# STM.net
KiCad netlist of a schematic drawn in Altium Designer
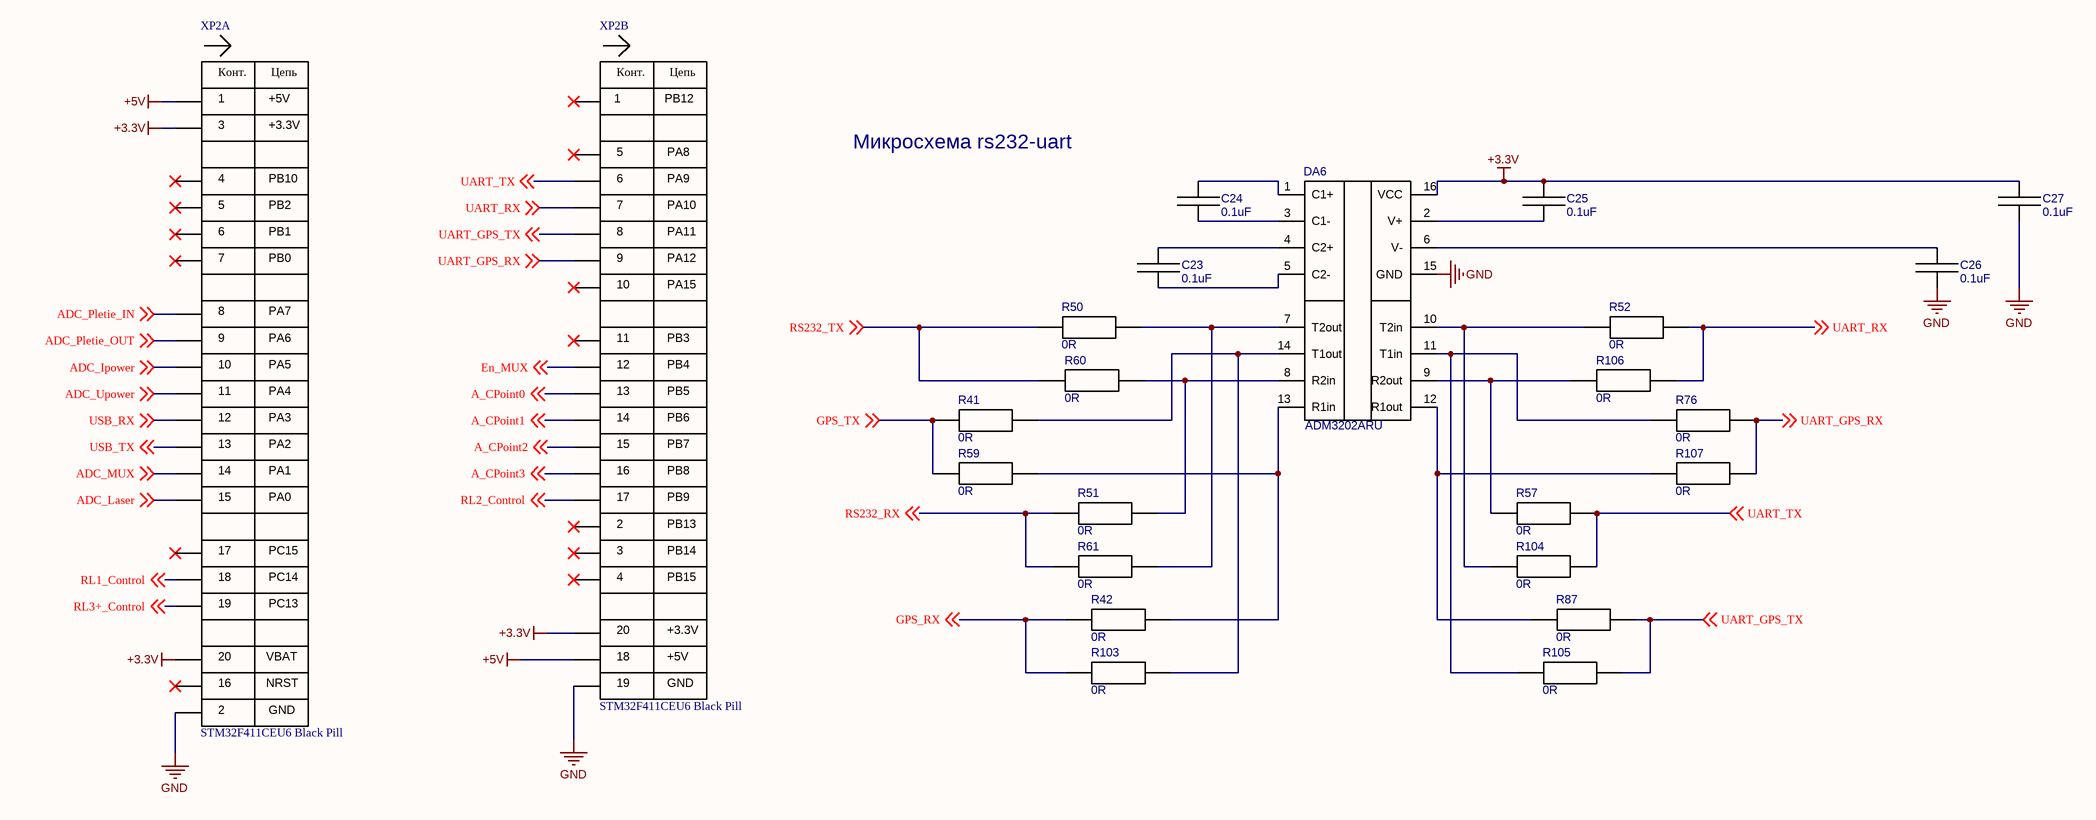
[diagram p0: STM.SchDoc]

(export (version "E")
  (design (tool "Eeschema 10.0.6"))
  (components
    (comp (ref "C23")
      (value "0.1uF")
      (footprint "0603C")
      (description "C0603 0.1UF 10% 50V")
      (fields
        (field (name "PART NUMBER") "SMD CAP CER 0.1UF ±10% 50V X7R 0603")
        (field (name "ADDED_BY") "anton@teslatec.ru")
      )
      (libsource (lib "Test_Stand_Pergam") (part "C0603-0.1UF 10% 50V"))
    )
    (comp (ref "C24")
      (value "0.1uF")
      (footprint "0603C")
      (description "C0603 0.1UF 10% 50V")
      (fields
        (field (name "PART NUMBER") "SMD CAP CER 0.1UF ±10% 50V X7R 0603")
        (field (name "ADDED_BY") "anton@teslatec.ru")
      )
      (libsource (lib "Test_Stand_Pergam") (part "C0603-0.1UF 10% 50V"))
    )
    (comp (ref "C25")
      (value "0.1uF")
      (footprint "0603C")
      (description "C0603 0.1UF 10% 50V")
      (fields
        (field (name "PART NUMBER") "SMD CAP CER 0.1UF ±10% 50V X7R 0603")
        (field (name "ADDED_BY") "anton@teslatec.ru")
      )
      (libsource (lib "Test_Stand_Pergam") (part "C0603-0.1UF 10% 50V"))
    )
    (comp (ref "C26")
      (value "0.1uF")
      (footprint "0603C")
      (description "C0603 0.1UF 10% 50V")
      (fields
        (field (name "PART NUMBER") "SMD CAP CER 0.1UF ±10% 50V X7R 0603")
        (field (name "ADDED_BY") "anton@teslatec.ru")
      )
      (libsource (lib "Test_Stand_Pergam") (part "C0603-0.1UF 10% 50V"))
    )
    (comp (ref "C27")
      (value "0.1uF")
      (footprint "0603C")
      (description "C0603 0.1UF 10% 50V")
      (fields
        (field (name "PART NUMBER") "SMD CAP CER 0.1UF ±10% 50V X7R 0603")
        (field (name "ADDED_BY") "anton@teslatec.ru")
      )
      (libsource (lib "Test_Stand_Pergam") (part "C0603-0.1UF 10% 50V"))
    )
    (comp (ref "DA6")
      (value "ADM3202ARU")
      (footprint "TSSOP-16")
      (description "Low Power, 3.3 V, RS-232\r\nLine Drivers/Receivers")
      (fields (field (name "ADDED_BY") "irdolgopolowa@yandex.ru"))
      (libsource (lib "Test_Stand_Pergam") (part "ADM3202ARU"))
    )
    (comp (ref "R41")
      (value "0R")
      (footprint "R0402")
      (description "Resistor SMD 0R 1% 0402")
      (fields
        (field (name "PART NUMBER") "SMD RES 0R 0402")
        (field (name "ADDED_BY") "irdolgopolowa@yandex.ru")
      )
      (libsource (lib "Test_Stand_Pergam") (part "R0402-0R"))
    )
    (comp (ref "R42")
      (value "0R")
      (footprint "R0402")
      (description "Resistor SMD 0R 1% 0402")
      (fields
        (field (name "PART NUMBER") "SMD RES 0R 0402")
        (field (name "ADDED_BY") "irdolgopolowa@yandex.ru")
      )
      (libsource (lib "Test_Stand_Pergam") (part "R0402-0R"))
    )
    (comp (ref "R50")
      (value "0R")
      (footprint "R0402")
      (description "Resistor SMD 0R 1% 0402")
      (fields
        (field (name "PART NUMBER") "SMD RES 0R 0402")
        (field (name "ADDED_BY") "irdolgopolowa@yandex.ru")
      )
      (libsource (lib "Test_Stand_Pergam") (part "R0402-0R"))
    )
    (comp (ref "R51")
      (value "0R")
      (footprint "R0402")
      (description "Resistor SMD 0R 1% 0402")
      (fields
        (field (name "PART NUMBER") "SMD RES 0R 0402")
        (field (name "ADDED_BY") "irdolgopolowa@yandex.ru")
      )
      (libsource (lib "Test_Stand_Pergam") (part "R0402-0R"))
    )
    (comp (ref "R52")
      (value "0R")
      (footprint "R0402")
      (description "Resistor SMD 0R 1% 0402")
      (fields
        (field (name "PART NUMBER") "SMD RES 0R 0402")
        (field (name "ADDED_BY") "irdolgopolowa@yandex.ru")
      )
      (libsource (lib "Test_Stand_Pergam") (part "R0402-0R"))
    )
    (comp (ref "R57")
      (value "0R")
      (footprint "R0402")
      (description "Resistor SMD 0R 1% 0402")
      (fields
        (field (name "PART NUMBER") "SMD RES 0R 0402")
        (field (name "ADDED_BY") "irdolgopolowa@yandex.ru")
      )
      (libsource (lib "Test_Stand_Pergam") (part "R0402-0R"))
    )
    (comp (ref "R59")
      (value "0R")
      (footprint "R0402")
      (description "Resistor SMD 0R 1% 0402")
      (fields
        (field (name "PART NUMBER") "SMD RES 0R 0402")
        (field (name "ADDED_BY") "irdolgopolowa@yandex.ru")
      )
      (libsource (lib "Test_Stand_Pergam") (part "R0402-0R"))
    )
    (comp (ref "R60")
      (value "0R")
      (footprint "R0402")
      (description "Resistor SMD 0R 1% 0402")
      (fields
        (field (name "PART NUMBER") "SMD RES 0R 0402")
        (field (name "ADDED_BY") "irdolgopolowa@yandex.ru")
      )
      (libsource (lib "Test_Stand_Pergam") (part "R0402-0R"))
    )
    (comp (ref "R61")
      (value "0R")
      (footprint "R0402")
      (description "Resistor SMD 0R 1% 0402")
      (fields
        (field (name "PART NUMBER") "SMD RES 0R 0402")
        (field (name "ADDED_BY") "irdolgopolowa@yandex.ru")
      )
      (libsource (lib "Test_Stand_Pergam") (part "R0402-0R"))
    )
    (comp (ref "R76")
      (value "0R")
      (footprint "R0402")
      (description "Resistor SMD 0R 1% 0402")
      (fields
        (field (name "PART NUMBER") "SMD RES 0R 0402")
        (field (name "ADDED_BY") "irdolgopolowa@yandex.ru")
      )
      (libsource (lib "Test_Stand_Pergam") (part "R0402-0R"))
    )
    (comp (ref "R87")
      (value "0R")
      (footprint "R0402")
      (description "Resistor SMD 0R 1% 0402")
      (fields
        (field (name "PART NUMBER") "SMD RES 0R 0402")
        (field (name "ADDED_BY") "irdolgopolowa@yandex.ru")
      )
      (libsource (lib "Test_Stand_Pergam") (part "R0402-0R"))
    )
    (comp (ref "R103")
      (value "0R")
      (footprint "R0402")
      (description "Resistor SMD 0R 1% 0402")
      (fields
        (field (name "PART NUMBER") "SMD RES 0R 0402")
        (field (name "ADDED_BY") "irdolgopolowa@yandex.ru")
      )
      (libsource (lib "Test_Stand_Pergam") (part "R0402-0R"))
    )
    (comp (ref "R104")
      (value "0R")
      (footprint "R0402")
      (description "Resistor SMD 0R 1% 0402")
      (fields
        (field (name "PART NUMBER") "SMD RES 0R 0402")
        (field (name "ADDED_BY") "irdolgopolowa@yandex.ru")
      )
      (libsource (lib "Test_Stand_Pergam") (part "R0402-0R"))
    )
    (comp (ref "R105")
      (value "0R")
      (footprint "R0402")
      (description "Resistor SMD 0R 1% 0402")
      (fields
        (field (name "PART NUMBER") "SMD RES 0R 0402")
        (field (name "ADDED_BY") "irdolgopolowa@yandex.ru")
      )
      (libsource (lib "Test_Stand_Pergam") (part "R0402-0R"))
    )
    (comp (ref "R106")
      (value "0R")
      (footprint "R0402")
      (description "Resistor SMD 0R 1% 0402")
      (fields
        (field (name "PART NUMBER") "SMD RES 0R 0402")
        (field (name "ADDED_BY") "irdolgopolowa@yandex.ru")
      )
      (libsource (lib "Test_Stand_Pergam") (part "R0402-0R"))
    )
    (comp (ref "R107")
      (value "0R")
      (footprint "R0402")
      (description "Resistor SMD 0R 1% 0402")
      (fields
        (field (name "PART NUMBER") "SMD RES 0R 0402")
        (field (name "ADDED_BY") "irdolgopolowa@yandex.ru")
      )
      (libsource (lib "Test_Stand_Pergam") (part "R0402-0R"))
    )
    (comp (ref "XP2")
      (value "STM32F411CEU6 Black Pill")
      (footprint "Black pill STM32F411CEU6")
      (description "STM32F411CEU6 Black pil")
      (fields
        (field (name "MATING PART") "2*DS1021-1*20SF11-B")
        (field (name "ADDED_BY") "irdolgopolowa@yandex.ru")
      )
      (libsource (lib "Test_Stand_Pergam") (part "STM32F411CEU6 Black pil"))
    )
  )
  (nets
    (net (code "1") (name "+3.3V") (class "Default")
      (node (ref "C25") (pin "2") (pinfunction "2_2") (pintype "passive"))
      (node (ref "C27") (pin "2") (pinfunction "2_2") (pintype "passive"))
      (node (ref "DA6") (pin "16") (pinfunction "VCC_16") (pintype "passive"))
      (node (ref "XP2") (pin "20") (pinfunction "VBAT_20") (pintype "passive"))
      (node (ref "XP2") (pin "3") (pinfunction "+3.3V_3") (pintype "passive"))
      (node (ref "XP2") (pin "40") (pinfunction "+3.3V_40") (pintype "passive"))
    )
    (net (code "2") (name "+5V") (class "Default")
      (node (ref "XP2") (pin "1") (pinfunction "+5V_1") (pintype "passive"))
      (node (ref "XP2") (pin "38") (pinfunction "+5V_38") (pintype "passive"))
    )
    (net (code "3") (name "ADC_Ipower") (class "Default")
      (node (ref "XP2") (pin "10") (pinfunction "PA5_10") (pintype "passive"))
    )
    (net (code "4") (name "ADC_Laser") (class "Default")
      (node (ref "XP2") (pin "15") (pinfunction "PA0_15") (pintype "passive"))
    )
    (net (code "5") (name "ADC_MUX") (class "Default")
      (node (ref "XP2") (pin "14") (pinfunction "PA1_14") (pintype "passive"))
    )
    (net (code "6") (name "ADC_Pletie_IN") (class "Default")
      (node (ref "XP2") (pin "8") (pinfunction "PA7_8") (pintype "passive"))
    )
    (net (code "7") (name "ADC_Pletie_OUT") (class "Default")
      (node (ref "XP2") (pin "9") (pinfunction "PA6_9") (pintype "passive"))
    )
    (net (code "8") (name "ADC_Upower") (class "Default")
      (node (ref "XP2") (pin "11") (pinfunction "PA4_11") (pintype "passive"))
    )
    (net (code "9") (name "A_CPoint0") (class "Default")
      (node (ref "XP2") (pin "33") (pinfunction "PB5_33") (pintype "passive"))
    )
    (net (code "10") (name "A_CPoint1") (class "Default")
      (node (ref "XP2") (pin "34") (pinfunction "PB6_34") (pintype "passive"))
    )
    (net (code "11") (name "A_CPoint2") (class "Default")
      (node (ref "XP2") (pin "35") (pinfunction "PB7_35") (pintype "passive"))
    )
    (net (code "12") (name "A_CPoint3") (class "Default")
      (node (ref "XP2") (pin "36") (pinfunction "PB8_36") (pintype "passive"))
    )
    (net (code "13") (name "En_MUX") (class "Default")
      (node (ref "XP2") (pin "32") (pinfunction "PB4_32") (pintype "passive"))
    )
    (net (code "14") (name "GND") (class "Default")
      (node (ref "C26") (pin "1") (pinfunction "1_1") (pintype "passive"))
      (node (ref "C27") (pin "1") (pinfunction "1_1") (pintype "passive"))
      (node (ref "DA6") (pin "15") (pinfunction "GND_15") (pintype "passive"))
      (node (ref "XP2") (pin "2") (pinfunction "GND_2") (pintype "passive"))
      (node (ref "XP2") (pin "39") (pinfunction "GND_39") (pintype "passive"))
    )
    (net (code "15") (name "GPS_RX") (class "Default")
      (node (ref "R103") (pin "1") (pinfunction "1_1") (pintype "passive"))
      (node (ref "R42") (pin "1") (pinfunction "1_1") (pintype "passive"))
    )
    (net (code "16") (name "GPS_TX") (class "Default")
      (node (ref "R41") (pin "1") (pinfunction "1_1") (pintype "passive"))
      (node (ref "R59") (pin "1") (pinfunction "1_1") (pintype "passive"))
    )
    (net (code "17") (name "Net-(DA6-C1+)") (class "Default")
      (node (ref "C24") (pin "2") (pinfunction "2_2") (pintype "passive"))
      (node (ref "DA6") (pin "1") (pinfunction "C1+_1") (pintype "passive"))
    )
    (net (code "18") (name "Net-(DA6-C1-)") (class "Default")
      (node (ref "C24") (pin "1") (pinfunction "1_1") (pintype "passive"))
      (node (ref "DA6") (pin "3") (pinfunction "C1-_3") (pintype "passive"))
    )
    (net (code "19") (name "Net-(DA6-C2+)") (class "Default")
      (node (ref "C23") (pin "2") (pinfunction "2_2") (pintype "passive"))
      (node (ref "DA6") (pin "4") (pinfunction "C2+_4") (pintype "passive"))
    )
    (net (code "20") (name "Net-(DA6-C2-)") (class "Default")
      (node (ref "C23") (pin "1") (pinfunction "1_1") (pintype "passive"))
      (node (ref "DA6") (pin "5") (pinfunction "C2-_5") (pintype "passive"))
    )
    (net (code "21") (name "Net-(DA6-R1in)") (class "Default")
      (node (ref "DA6") (pin "13") (pinfunction "R1in_13") (pintype "passive"))
      (node (ref "R42") (pin "2") (pinfunction "2_2") (pintype "passive"))
      (node (ref "R59") (pin "2") (pinfunction "2_2") (pintype "passive"))
    )
    (net (code "22") (name "Net-(DA6-R1out)") (class "Default")
      (node (ref "DA6") (pin "12") (pinfunction "R1out_12") (pintype "passive"))
      (node (ref "R107") (pin "1") (pinfunction "1_1") (pintype "passive"))
      (node (ref "R87") (pin "1") (pinfunction "1_1") (pintype "passive"))
    )
    (net (code "23") (name "Net-(DA6-R2in)") (class "Default")
      (node (ref "DA6") (pin "8") (pinfunction "R2in_8") (pintype "passive"))
      (node (ref "R51") (pin "2") (pinfunction "2_2") (pintype "passive"))
      (node (ref "R60") (pin "2") (pinfunction "2_2") (pintype "passive"))
    )
    (net (code "24") (name "Net-(DA6-R2out)") (class "Default")
      (node (ref "DA6") (pin "9") (pinfunction "R2out_9") (pintype "passive"))
      (node (ref "R106") (pin "1") (pinfunction "1_1") (pintype "passive"))
      (node (ref "R57") (pin "1") (pinfunction "1_1") (pintype "passive"))
    )
    (net (code "25") (name "Net-(DA6-T1in)") (class "Default")
      (node (ref "DA6") (pin "11") (pinfunction "T1in_11") (pintype "passive"))
      (node (ref "R105") (pin "1") (pinfunction "1_1") (pintype "passive"))
      (node (ref "R76") (pin "1") (pinfunction "1_1") (pintype "passive"))
    )
    (net (code "26") (name "Net-(DA6-T1out)") (class "Default")
      (node (ref "DA6") (pin "14") (pinfunction "T1out_14") (pintype "passive"))
      (node (ref "R103") (pin "2") (pinfunction "2_2") (pintype "passive"))
      (node (ref "R41") (pin "2") (pinfunction "2_2") (pintype "passive"))
    )
    (net (code "27") (name "Net-(DA6-T2in)") (class "Default")
      (node (ref "DA6") (pin "10") (pinfunction "T2in_10") (pintype "passive"))
      (node (ref "R104") (pin "1") (pinfunction "1_1") (pintype "passive"))
      (node (ref "R52") (pin "1") (pinfunction "1_1") (pintype "passive"))
    )
    (net (code "28") (name "Net-(DA6-T2out)") (class "Default")
      (node (ref "DA6") (pin "7") (pinfunction "T2out_7") (pintype "passive"))
      (node (ref "R50") (pin "2") (pinfunction "2_2") (pintype "passive"))
      (node (ref "R61") (pin "2") (pinfunction "2_2") (pintype "passive"))
    )
    (net (code "29") (name "Net-(DA6-V+)") (class "Default")
      (node (ref "C25") (pin "1") (pinfunction "1_1") (pintype "passive"))
      (node (ref "DA6") (pin "2") (pinfunction "V+_2") (pintype "passive"))
    )
    (net (code "30") (name "Net-(DA6-V-)") (class "Default")
      (node (ref "C26") (pin "2") (pinfunction "2_2") (pintype "passive"))
      (node (ref "DA6") (pin "6") (pinfunction "V-_6") (pintype "passive"))
    )
    (net (code "31") (name "RL1_Control") (class "Default")
      (node (ref "XP2") (pin "18") (pinfunction "PC14_18") (pintype "passive"))
    )
    (net (code "32") (name "RL2_Control") (class "Default")
      (node (ref "XP2") (pin "37") (pinfunction "PB9_37") (pintype "passive"))
    )
    (net (code "33") (name "RL3+_Control") (class "Default")
      (node (ref "XP2") (pin "19") (pinfunction "PC13_19") (pintype "passive"))
    )
    (net (code "34") (name "RS232_RX") (class "Default")
      (node (ref "R51") (pin "1") (pinfunction "1_1") (pintype "passive"))
      (node (ref "R61") (pin "1") (pinfunction "1_1") (pintype "passive"))
    )
    (net (code "35") (name "RS232_TX") (class "Default")
      (node (ref "R50") (pin "1") (pinfunction "1_1") (pintype "passive"))
      (node (ref "R60") (pin "1") (pinfunction "1_1") (pintype "passive"))
    )
    (net (code "36") (name "UART_GPS_RX") (class "Default")
      (node (ref "R107") (pin "2") (pinfunction "2_2") (pintype "passive"))
      (node (ref "R76") (pin "2") (pinfunction "2_2") (pintype "passive"))
      (node (ref "XP2") (pin "29") (pinfunction "PA12_29") (pintype "passive"))
    )
    (net (code "37") (name "UART_GPS_TX") (class "Default")
      (node (ref "R105") (pin "2") (pinfunction "2_2") (pintype "passive"))
      (node (ref "R87") (pin "2") (pinfunction "2_2") (pintype "passive"))
      (node (ref "XP2") (pin "28") (pinfunction "PA11_28") (pintype "passive"))
    )
    (net (code "38") (name "UART_RX") (class "Default")
      (node (ref "R106") (pin "2") (pinfunction "2_2") (pintype "passive"))
      (node (ref "R52") (pin "2") (pinfunction "2_2") (pintype "passive"))
      (node (ref "XP2") (pin "27") (pinfunction "PA10_27") (pintype "passive"))
    )
    (net (code "39") (name "UART_TX") (class "Default")
      (node (ref "R104") (pin "2") (pinfunction "2_2") (pintype "passive"))
      (node (ref "R57") (pin "2") (pinfunction "2_2") (pintype "passive"))
      (node (ref "XP2") (pin "26") (pinfunction "PA9_26") (pintype "passive"))
    )
    (net (code "40") (name "USB_RX") (class "Default")
      (node (ref "XP2") (pin "12") (pinfunction "PA3_12") (pintype "passive"))
    )
    (net (code "41") (name "USB_TX") (class "Default")
      (node (ref "XP2") (pin "13") (pinfunction "PA2_13") (pintype "passive"))
    )
    (net (code "42") (name "unconnected-(XP2A-NRST-Pad16)") (class "Default")
      (node (ref "XP2") (pin "16") (pinfunction "NRST_16") (pintype "passive+no_connect"))
    )
    (net (code "43") (name "unconnected-(XP2A-PB0-Pad7)") (class "Default")
      (node (ref "XP2") (pin "7") (pinfunction "PB0_7") (pintype "passive+no_connect"))
    )
    (net (code "44") (name "unconnected-(XP2A-PB1-Pad6)") (class "Default")
      (node (ref "XP2") (pin "6") (pinfunction "PB1_6") (pintype "passive+no_connect"))
    )
    (net (code "45") (name "unconnected-(XP2A-PB2-Pad5)") (class "Default")
      (node (ref "XP2") (pin "5") (pinfunction "PB2_5") (pintype "passive+no_connect"))
    )
    (net (code "46") (name "unconnected-(XP2A-PB10-Pad4)") (class "Default")
      (node (ref "XP2") (pin "4") (pinfunction "PB10_4") (pintype "passive+no_connect"))
    )
    (net (code "47") (name "unconnected-(XP2A-PC15-Pad17)") (class "Default")
      (node (ref "XP2") (pin "17") (pinfunction "PC15_17") (pintype "passive+no_connect"))
    )
    (net (code "48") (name "unconnected-(XP2B-PA8-Pad25)") (class "Default")
      (node (ref "XP2") (pin "25") (pinfunction "PA8_25") (pintype "passive+no_connect"))
    )
    (net (code "49") (name "unconnected-(XP2B-PA15-Pad30)") (class "Default")
      (node (ref "XP2") (pin "30") (pinfunction "PA15_30") (pintype "passive+no_connect"))
    )
    (net (code "50") (name "unconnected-(XP2B-PB3-Pad31)") (class "Default")
      (node (ref "XP2") (pin "31") (pinfunction "PB3_31") (pintype "passive+no_connect"))
    )
    (net (code "51") (name "unconnected-(XP2B-PB12-Pad21)") (class "Default")
      (node (ref "XP2") (pin "21") (pinfunction "PB12_21") (pintype "passive+no_connect"))
    )
    (net (code "52") (name "unconnected-(XP2B-PB13-Pad22)") (class "Default")
      (node (ref "XP2") (pin "22") (pinfunction "PB13_22") (pintype "passive+no_connect"))
    )
    (net (code "53") (name "unconnected-(XP2B-PB14-Pad23)") (class "Default")
      (node (ref "XP2") (pin "23") (pinfunction "PB14_23") (pintype "passive+no_connect"))
    )
    (net (code "54") (name "unconnected-(XP2B-PB15-Pad24)") (class "Default")
      (node (ref "XP2") (pin "24") (pinfunction "PB15_24") (pintype "passive+no_connect"))
    )
  )
)
